# Sheet1.net
KiCad netlist of a schematic drawn in Altium Designer
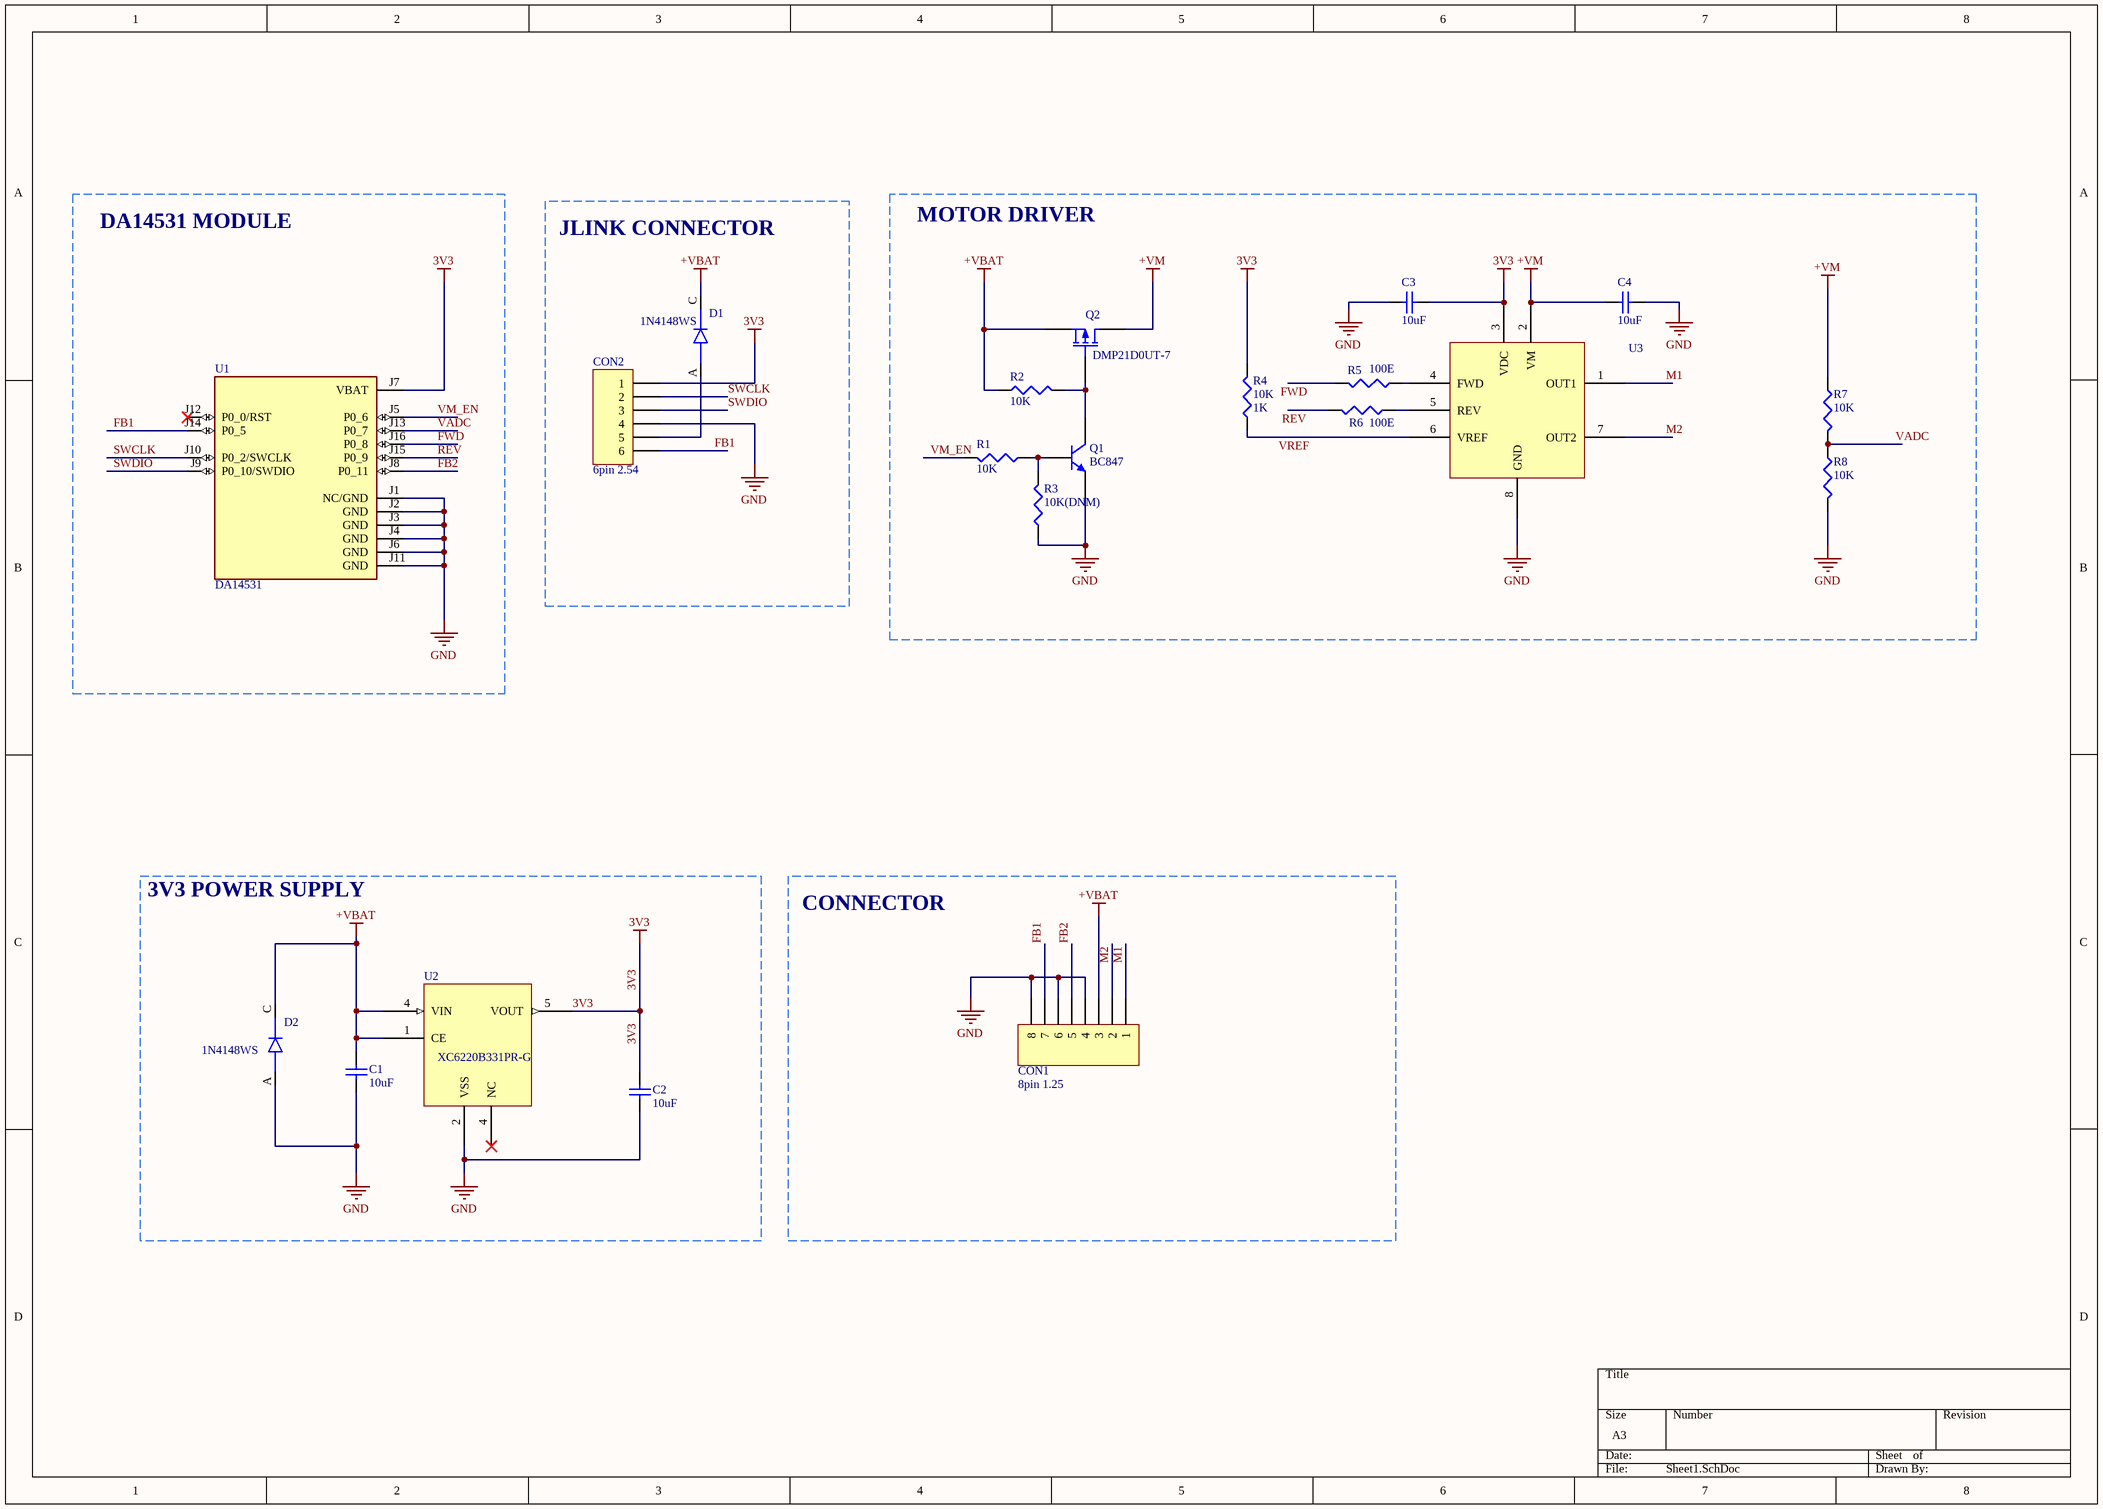
[diagram p0: Sheet1.SchDoc]

(export (version "E")
  (design (tool "Eeschema 10.0.6"))
  (components
    (comp (ref "C1")
      (value "10uF")
      (footprint "0603_C")
      (description "Capacitor")
      (fields (field (name "MFR") "KEMET"))
      (libsource (lib "Miscellaneous Devices") (part "Cap"))
    )
    (comp (ref "C2")
      (value "10uF")
      (footprint "0603_C")
      (description "Capacitor")
      (fields (field (name "MFR") "KEMET"))
      (libsource (lib "Miscellaneous Devices") (part "Cap"))
    )
    (comp (ref "C3")
      (value "10uF")
      (footprint "0603_C")
      (description "Capacitor")
      (fields (field (name "MFR") "KEMET"))
      (libsource (lib "Miscellaneous Devices") (part "Cap"))
    )
    (comp (ref "C4")
      (value "10uF")
      (footprint "0603_C")
      (description "Capacitor")
      (fields (field (name "MFR") "KEMET"))
      (libsource (lib "Miscellaneous Devices") (part "Cap"))
    )
    (comp (ref "CON1")
      (value "8pin 1.25")
      (footprint "8Pin 1.25mm SMT")
      (libsource (lib "XC6220B331PR-G_SCH") (part "8pin 1.25"))
    )
    (comp (ref "CON2")
      (value "6pin 2.54")
      (footprint "6PIN 2.54")
      (libsource (lib "XC6220B331PR-G_SCH") (part "6pin 2.54"))
    )
    (comp (ref "D1")
      (value "1N4148WS")
      (footprint "SOD323")
      (description "Diode Standard 100V 150mA Surface Mount SOD-123")
      (fields (field (name "MF") "Micro Commercial") (field (name "MP") "1N4148W-TP"))
      (libsource (lib "XC6220B331PR-G_SCH") (part "1N4148W-TP"))
    )
    (comp (ref "D2")
      (value "1N4148WS")
      (footprint "SOD323")
      (description "Diode Standard 100V 150mA Surface Mount SOD-123")
      (fields (field (name "MF") "Micro Commercial") (field (name "MP") "1N4148W-TP"))
      (libsource (lib "XC6220B331PR-G_SCH") (part "1N4148W-TP"))
    )
    (comp (ref "Q1")
      (value "BC847")
      (footprint "BC846")
      (fields (field (name "MFR") "Nexperia"))
      (libsource (lib "XC6220B331PR-G_SCH") (part "BC846X"))
    )
    (comp (ref "Q2")
      (value "Q2")
      (footprint "SOT_523_P_MOS")
      (fields (field (name "PN") "DMP21D0UT-7") (field (name "MFR") "Diodes Incorporated"))
      (libsource (lib "XC6220B331PR-G_SCH") (part "PMOS"))
    )
    (comp (ref "R1")
      (value "10K")
      (footprint "0603_R")
      (description "Resistor")
      (libsource (lib "XC6220B331PR-G_SCH") (part "Res3"))
    )
    (comp (ref "R2")
      (value "10K")
      (footprint "0603_R")
      (description "Resistor")
      (libsource (lib "XC6220B331PR-G_SCH") (part "Res3"))
    )
    (comp (ref "R3")
      (value "10K(DNM)")
      (footprint "0603_R")
      (description "Resistor")
      (libsource (lib "XC6220B331PR-G_SCH") (part "Res3"))
    )
    (comp (ref "R4")
      (value "10K")
      (footprint "0603_R")
      (description "Resistor")
      (fields (field (name "ALTIUM_VALUE") "1K") (field (name "PUBLISHER") "Altium Limited"))
      (libsource (lib "XC6220B331PR-G_SCH") (part "Res3"))
    )
    (comp (ref "R5")
      (value "100E")
      (footprint "0603_R")
      (description "Resistor")
      (libsource (lib "XC6220B331PR-G_SCH") (part "Res3"))
    )
    (comp (ref "R6")
      (value "100E")
      (footprint "0603_R")
      (description "Resistor")
      (libsource (lib "XC6220B331PR-G_SCH") (part "Res3"))
    )
    (comp (ref "R7")
      (value "10K")
      (footprint "0603_R")
      (description "Resistor")
      (libsource (lib "XC6220B331PR-G_SCH") (part "Res3"))
    )
    (comp (ref "R8")
      (value "10K")
      (footprint "0603_R")
      (description "Resistor")
      (libsource (lib "XC6220B331PR-G_SCH") (part "Res3"))
    )
    (comp (ref "U1")
      (value "DA14531")
      (footprint "DA14531")
      (fields (field (name "MFR") "Dialog Semiconductor"))
      (libsource (lib "XC6220B331PR-G_SCH") (part "DA14531"))
    )
    (comp (ref "U2")
      (value "XC6220B331PR-G")
      (footprint "CONV_AL8861Y-13")
      (fields (field (name "MFR") "Torex Semiconductor Ltd"))
      (libsource (lib "XC6220B331PR-G_SCH") (part "Component_1"))
    )
    (comp (ref "U3")
      (value "ZXBM5210")
      (footprint "SOIC127P600X180-8N")
      (libsource (lib "XC6220B331PR-G_SCH") (part "ZXBM5210"))
    )
  )
  (nets
    (net (code "1") (name "+VBAT") (class "Default")
      (node (ref "C1") (pin "2") (pinfunction "2_2") (pintype "passive"))
      (node (ref "CON1") (pin "3") (pinfunction "3_3") (pintype "passive"))
      (node (ref "D1") (pin "C") (pinfunction "C_C") (pintype "passive"))
      (node (ref "D2") (pin "C") (pinfunction "C_C") (pintype "passive"))
      (node (ref "Q2") (pin "3") (pinfunction "S_3") (pintype "passive"))
      (node (ref "R2") (pin "1") (pinfunction "1_1") (pintype "passive"))
      (node (ref "U2") (pin "1") (pinfunction "CE_1") (pintype "passive"))
      (node (ref "U2") (pin "4") (pinfunction "VIN_4") (pintype "input"))
    )
    (net (code "2") (name "+VM") (class "Default")
      (node (ref "C4") (pin "2") (pinfunction "2_2") (pintype "passive"))
      (node (ref "Q2") (pin "1") (pinfunction "D_1") (pintype "passive"))
      (node (ref "R7") (pin "1") (pinfunction "1_1") (pintype "passive"))
      (node (ref "U3") (pin "2") (pinfunction "VM_2") (pintype "passive"))
    )
    (net (code "3") (name "/FB1") (class "Default")
      (node (ref "CON1") (pin "7") (pinfunction "7_7") (pintype "passive"))
      (node (ref "CON2") (pin "6") (pinfunction "6_6") (pintype "passive"))
      (node (ref "U1") (pin "J14") (pinfunction "P0_5_J14") (pintype "bidirectional"))
    )
    (net (code "4") (name "/FB2") (class "Default")
      (node (ref "CON1") (pin "5") (pinfunction "5_5") (pintype "passive"))
      (node (ref "U1") (pin "J8") (pinfunction "P0_11_J8") (pintype "bidirectional"))
    )
    (net (code "5") (name "/FWD") (class "Default")
      (node (ref "R5") (pin "2") (pinfunction "2_2") (pintype "passive"))
      (node (ref "U1") (pin "J16") (pinfunction "P0_8_J16") (pintype "bidirectional"))
    )
    (net (code "6") (name "/M1") (class "Default")
      (node (ref "CON1") (pin "1") (pinfunction "1_1") (pintype "passive"))
      (node (ref "U3") (pin "1") (pinfunction "OUT1_1") (pintype "passive"))
    )
    (net (code "7") (name "/M2") (class "Default")
      (node (ref "CON1") (pin "2") (pinfunction "2_2") (pintype "passive"))
      (node (ref "U3") (pin "7") (pinfunction "OUT2_7") (pintype "passive"))
    )
    (net (code "8") (name "/REV") (class "Default")
      (node (ref "R6") (pin "2") (pinfunction "2_2") (pintype "passive"))
      (node (ref "U1") (pin "J15") (pinfunction "P0_9_J15") (pintype "bidirectional"))
    )
    (net (code "9") (name "/SWCLK") (class "Default")
      (node (ref "CON2") (pin "2") (pinfunction "2_2") (pintype "passive"))
      (node (ref "U1") (pin "J10") (pinfunction "P0_2/SWCLK_J10") (pintype "bidirectional"))
    )
    (net (code "10") (name "/SWDIO") (class "Default")
      (node (ref "CON2") (pin "3") (pinfunction "3_3") (pintype "passive"))
      (node (ref "U1") (pin "J9") (pinfunction "P0_10/SWDIO_J9") (pintype "bidirectional"))
    )
    (net (code "11") (name "/VADC") (class "Default")
      (node (ref "R7") (pin "2") (pinfunction "2_2") (pintype "passive"))
      (node (ref "R8") (pin "1") (pinfunction "1_1") (pintype "passive"))
      (node (ref "U1") (pin "J13") (pinfunction "P0_7_J13") (pintype "bidirectional"))
    )
    (net (code "12") (name "/VM_EN") (class "Default")
      (node (ref "R1") (pin "2") (pinfunction "2_2") (pintype "passive"))
      (node (ref "U1") (pin "J5") (pinfunction "P0_6_J5") (pintype "bidirectional"))
    )
    (net (code "13") (name "/VREF") (class "Default")
      (node (ref "R4") (pin "1") (pinfunction "1_1") (pintype "passive"))
      (node (ref "U3") (pin "6") (pinfunction "VREF_6") (pintype "passive"))
    )
    (net (code "14") (name "3V3") (class "Default")
      (node (ref "C2") (pin "2") (pinfunction "2_2") (pintype "passive"))
      (node (ref "C3") (pin "2") (pinfunction "2_2") (pintype "passive"))
      (node (ref "CON2") (pin "1") (pinfunction "1_1") (pintype "passive"))
      (node (ref "R4") (pin "2") (pinfunction "2_2") (pintype "passive"))
      (node (ref "U1") (pin "J7") (pinfunction "VBAT_J7") (pintype "power_in"))
      (node (ref "U2") (pin "5") (pinfunction "VOUT_5") (pintype "output"))
      (node (ref "U3") (pin "3") (pinfunction "VDC_3") (pintype "passive"))
    )
    (net (code "15") (name "GND") (class "Default")
      (node (ref "C1") (pin "1") (pinfunction "1_1") (pintype "passive"))
      (node (ref "C2") (pin "1") (pinfunction "1_1") (pintype "passive"))
      (node (ref "C3") (pin "1") (pinfunction "1_1") (pintype "passive"))
      (node (ref "C4") (pin "1") (pinfunction "1_1") (pintype "passive"))
      (node (ref "CON1") (pin "4") (pinfunction "4_4") (pintype "passive"))
      (node (ref "CON1") (pin "6") (pinfunction "6_6") (pintype "passive"))
      (node (ref "CON1") (pin "8") (pinfunction "8_8") (pintype "passive"))
      (node (ref "CON2") (pin "4") (pinfunction "4_4") (pintype "passive"))
      (node (ref "D2") (pin "A") (pinfunction "A_A") (pintype "passive"))
      (node (ref "Q1") (pin "2") (pinfunction "E_2") (pintype "passive"))
      (node (ref "R3") (pin "1") (pinfunction "1_1") (pintype "passive"))
      (node (ref "R8") (pin "2") (pinfunction "2_2") (pintype "passive"))
      (node (ref "U1") (pin "J1") (pinfunction "NC/GND_J1") (pintype "passive"))
      (node (ref "U1") (pin "J11") (pinfunction "GND_J11") (pintype "power_in"))
      (node (ref "U1") (pin "J2") (pinfunction "GND_J2") (pintype "power_in"))
      (node (ref "U1") (pin "J3") (pinfunction "GND_J3") (pintype "power_in"))
      (node (ref "U1") (pin "J4") (pinfunction "GND_J4") (pintype "power_in"))
      (node (ref "U1") (pin "J6") (pinfunction "GND_J6") (pintype "power_in"))
      (node (ref "U2") (pin "2") (pinfunction "VSS_2") (pintype "passive"))
      (node (ref "U3") (pin "8") (pinfunction "GND_8") (pintype "passive"))
    )
    (net (code "16") (name "Net-(CON2-Pad5)") (class "Default")
      (node (ref "CON2") (pin "5") (pinfunction "5_5") (pintype "passive"))
      (node (ref "D1") (pin "A") (pinfunction "A_A") (pintype "passive"))
    )
    (net (code "17") (name "Net-(Q1-B)") (class "Default")
      (node (ref "Q1") (pin "3") (pinfunction "B_3") (pintype "passive"))
      (node (ref "R1") (pin "1") (pinfunction "1_1") (pintype "passive"))
      (node (ref "R3") (pin "2") (pinfunction "2_2") (pintype "passive"))
    )
    (net (code "18") (name "Net-(Q1-C)") (class "Default")
      (node (ref "Q1") (pin "1") (pinfunction "C_1") (pintype "passive"))
      (node (ref "Q2") (pin "2") (pinfunction "G_2") (pintype "passive"))
      (node (ref "R2") (pin "2") (pinfunction "2_2") (pintype "passive"))
    )
    (net (code "19") (name "Net-(U3-FWD)") (class "Default")
      (node (ref "R5") (pin "1") (pinfunction "1_1") (pintype "passive"))
      (node (ref "U3") (pin "4") (pinfunction "FWD_4") (pintype "passive"))
    )
    (net (code "20") (name "Net-(U3-REV)") (class "Default")
      (node (ref "R6") (pin "1") (pinfunction "1_1") (pintype "passive"))
      (node (ref "U3") (pin "5") (pinfunction "REV_5") (pintype "passive"))
    )
    (net (code "21") (name "unconnected-(U1-P0_0{slash}RST-PadJ12)") (class "Default")
      (node (ref "U1") (pin "J12") (pinfunction "P0_0/RST_J12") (pintype "bidirectional+no_connect"))
    )
    (net (code "22") (name "unconnected-(U2-NC-Pad4)") (class "Default")
      (node (ref "U2") (pin "4") (pinfunction "NC_4") (pintype "passive+no_connect"))
    )
  )
)
